# Boost_converter.net
KiCad netlist of a schematic drawn in EAGLE
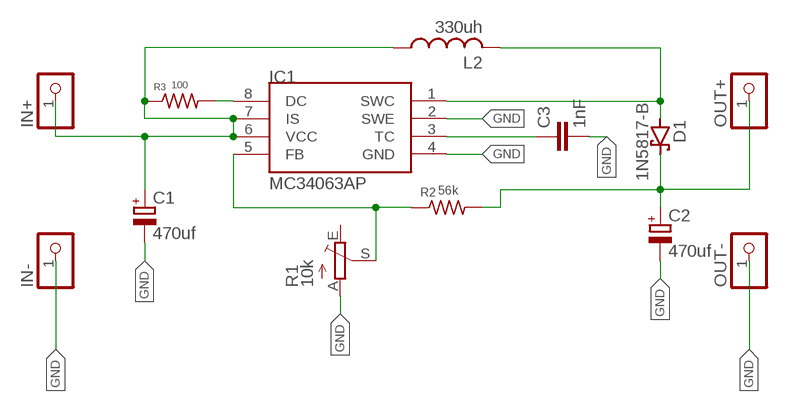
[diagram p0: schematic, sheet 1]

(export (version "E")
  (design (tool "Eeschema 10.0.6"))
  (components
    (comp (ref "C1")
      (value "470uf")
      (footprint "eagle-import:E3,5-8")
      (libsource (lib "eagle-import") (part "CAP_POL"))
    )
    (comp (ref "C2")
      (value "470uf")
      (footprint "eagle-import:E3,5-8")
      (libsource (lib "eagle-import") (part "CAP_POL"))
    )
    (comp (ref "C3")
      (value "1nF")
      (footprint "eagle-import:C025-025X050")
      (libsource (lib "eagle-import") (part "CAPACITOR"))
    )
    (comp (ref "D1")
      (value "1N5817-B")
      (footprint "eagle-import:DO41-7.6")
      (libsource (lib "eagle-import") (part "1N5817-B"))
    )
    (comp (ref "IC1")
      (value "MC34063AP")
      (footprint "eagle-import:DIL08")
      (libsource (lib "eagle-import") (part "MC34063AP"))
    )
    (comp (ref "IN+")
      (value "PINHD-1X1")
      (footprint "eagle-import:1X01")
      (libsource (lib "eagle-import") (part "PINHD-1X1"))
    )
    (comp (ref "IN-")
      (value "PINHD-1X1")
      (footprint "eagle-import:1X01")
      (libsource (lib "eagle-import") (part "PINHD-1X1"))
    )
    (comp (ref "L2")
      (value "330uh")
      (footprint "eagle-import:0207_10")
      (libsource (lib "eagle-import") (part "L-US0207/10"))
    )
    (comp (ref "OUT+")
      (value "PINHD-1X1")
      (footprint "eagle-import:1X01")
      (libsource (lib "eagle-import") (part "PINHD-1X1"))
    )
    (comp (ref "OUT-")
      (value "PINHD-1X1")
      (footprint "eagle-import:1X01")
      (libsource (lib "eagle-import") (part "PINHD-1X1"))
    )
    (comp (ref "R1")
      (value "10k")
      (footprint "eagle-import:CA6V")
      (libsource (lib "eagle-import") (part "TRIM_EU-CA6V"))
    )
    (comp (ref "R2")
      (value "56k")
      (footprint "eagle-import:0204_7")
      (libsource (lib "eagle-import") (part "RES-7"))
    )
    (comp (ref "R3")
      (value "100")
      (footprint "eagle-import:0204_7")
      (libsource (lib "eagle-import") (part "RES-7"))
    )
  )
  (nets
    (net (code "1") (name "GND") (class "Default")
      (node (ref "C1") (pin "-") (pinfunction "-_-") (pintype "passive"))
      (node (ref "C2") (pin "-") (pinfunction "-_-") (pintype "passive"))
      (node (ref "C3") (pin "2") (pinfunction "2_2") (pintype "passive"))
      (node (ref "IC1") (pin "2") (pinfunction "SWE_2") (pintype "passive"))
      (node (ref "IC1") (pin "4") (pinfunction "GND_4") (pintype "passive"))
      (node (ref "IN-") (pin "1") (pinfunction "1_1") (pintype "passive"))
      (node (ref "OUT-") (pin "1") (pinfunction "1_1") (pintype "passive"))
      (node (ref "R1") (pin "A") (pinfunction "A_A") (pintype "passive"))
    )
    (net (code "2") (name "Net-(C2-Pad+)") (class "Default")
      (node (ref "C2") (pin "+") (pinfunction "+_+") (pintype "passive"))
      (node (ref "D1") (pin "C") (pinfunction "C_C") (pintype "passive"))
      (node (ref "OUT+") (pin "1") (pinfunction "1_1") (pintype "passive"))
      (node (ref "R2") (pin "2") (pinfunction "2_2") (pintype "passive"))
    )
    (net (code "3") (name "Net-(IC1-DC)") (class "Default")
      (node (ref "IC1") (pin "8") (pinfunction "DC_8") (pintype "passive"))
      (node (ref "R3") (pin "2") (pinfunction "2_2") (pintype "passive"))
    )
    (net (code "4") (name "Net-(IC1-FB)") (class "Default")
      (node (ref "IC1") (pin "5") (pinfunction "FB_5") (pintype "passive"))
      (node (ref "R1") (pin "S") (pinfunction "S_S") (pintype "passive"))
      (node (ref "R2") (pin "1") (pinfunction "1_1") (pintype "passive"))
    )
    (net (code "5") (name "Net-(IC1-IS)") (class "Default")
      (node (ref "C1") (pin "+") (pinfunction "+_+") (pintype "passive"))
      (node (ref "IC1") (pin "6") (pinfunction "VCC_6") (pintype "passive"))
      (node (ref "IC1") (pin "7") (pinfunction "IS_7") (pintype "passive"))
      (node (ref "IN+") (pin "1") (pinfunction "1_1") (pintype "passive"))
      (node (ref "L2") (pin "1") (pinfunction "1_1") (pintype "passive"))
      (node (ref "R3") (pin "1") (pinfunction "1_1") (pintype "passive"))
    )
    (net (code "6") (name "Net-(IC1-SWC)") (class "Default")
      (node (ref "D1") (pin "A") (pinfunction "A_A") (pintype "passive"))
      (node (ref "IC1") (pin "1") (pinfunction "SWC_1") (pintype "passive"))
      (node (ref "L2") (pin "2") (pinfunction "2_2") (pintype "passive"))
    )
    (net (code "7") (name "Net-(IC1-TC)") (class "Default")
      (node (ref "C3") (pin "1") (pinfunction "1_1") (pintype "passive"))
      (node (ref "IC1") (pin "3") (pinfunction "TC_3") (pintype "passive"))
    )
    (net (code "8") (name "unconnected-(R1-PadE)") (class "Default")
      (node (ref "R1") (pin "E") (pinfunction "E_E") (pintype "passive"))
    )
  )
)
